# Sht1-Schem.net
KiCad netlist of a schematic drawn in Altium Designer
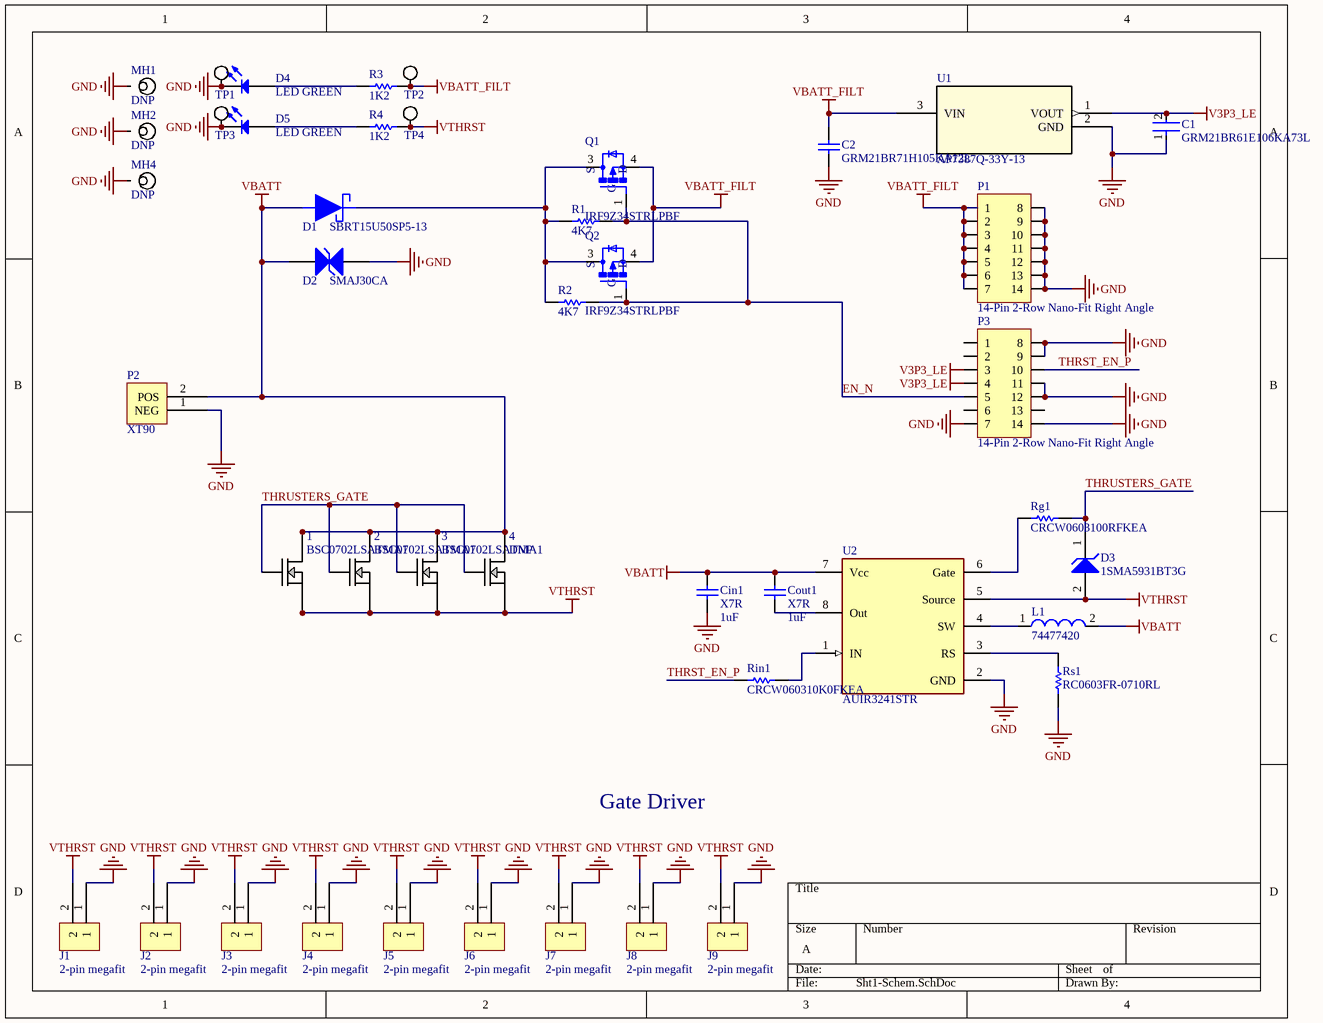
[diagram p0: Sht1-Schem.SchDoc]

(export (version "E")
  (design (tool "Eeschema 10.0.6"))
  (components
    (comp (ref "1")
      (value "BSC0702LSATMA1")
      (footprint "TRANS_NexFET_Q5A")
      (description "No Description Available")
      (fields
        (field (name "MANUFACTURER_PART_NUMBER") "CSD18537NQ5A")
        (field (name "COPYRIGHT") "Copyright (C) 2018 Accelerated Designs. All rights reserved")
      )
      (libsource (lib "TAUV-Lib") (part "BSC0702LSATMA1"))
    )
    (comp (ref "2")
      (value "BSC0702LSATMA1")
      (footprint "TRANS_NexFET_Q5A")
      (description "No Description Available")
      (fields
        (field (name "MANUFACTURER_PART_NUMBER") "CSD18537NQ5A")
        (field (name "COPYRIGHT") "Copyright (C) 2018 Accelerated Designs. All rights reserved")
      )
      (libsource (lib "TAUV-Lib") (part "BSC0702LSATMA1"))
    )
    (comp (ref "3")
      (value "BSC0702LSATMA1")
      (footprint "TRANS_NexFET_Q5A")
      (description "No Description Available")
      (fields
        (field (name "MANUFACTURER_PART_NUMBER") "CSD18537NQ5A")
        (field (name "COPYRIGHT") "Copyright (C) 2018 Accelerated Designs. All rights reserved")
      )
      (libsource (lib "TAUV-Lib") (part "BSC0702LSATMA1"))
    )
    (comp (ref "4")
      (value "DNP")
      (footprint "TRANS_NexFET_Q5A")
      (description "No Description Available")
      (fields
        (field (name "MANUFACTURER_PART_NUMBER") "CSD18537NQ5A")
        (field (name "COPYRIGHT") "Copyright (C) 2018 Accelerated Designs. All rights reserved")
      )
      (libsource (lib "TAUV-Lib") (part "BSC0702LSATMA1"))
    )
    (comp (ref "C1")
      (value "GRM21BR61E106KA73L")
      (footprint "FP-GRM21B-0_15-IPC_C")
      (description "Chip Multilayer Ceramic Capacitors for General Purpose, 0805, 10uF, X5R, 15%, 10%, 25V")
      (fields (field (name "VOLTAGE") "25V") (field (name "TOLERANCE") "10%"))
      (libsource (lib "Altium Content Vault") (part "b4654b650e69147ec39a6b967a45e02"))
    )
    (comp (ref "C2")
      (value "GRM21BR71H105KA12L")
      (footprint "CAPC2013X135X45LL10T25")
      (description "1uF")
      (fields (field (name "MANUFACTURER") "Murata"))
      (libsource (lib "Altium Content Vault") (part "CAP"))
    )
    (comp (ref "Cin1")
      (value "X7R")
      (footprint "C0805")
      (description "Capacitor")
      (fields (field (name "ALTIUM_VALUE") "1uF") (field (name "PUBLISHER") "Altium Limited"))
      (libsource (lib "Miscellaneous Devices") (part "Cap"))
    )
    (comp (ref "Cout1")
      (value "X7R")
      (footprint "C0805")
      (description "Capacitor")
      (fields (field (name "ALTIUM_VALUE") "1uF") (field (name "PUBLISHER") "Altium Limited"))
      (libsource (lib "Miscellaneous Devices") (part "Cap"))
    )
    (comp (ref "D1")
      (value "SBRT15U50SP5-13")
      (footprint "SBRT15U50SP5-13")
      (fields (field (name "MANUFACTURER") "Diodes Incorporated"))
      (libsource (lib "CMR_Miscellaneous_Devices") (part "SBRT15U50SP5-13"))
    )
    (comp (ref "D2")
      (value "SMAJ30CA")
      (footprint "LFUS-DO-214AC-A-2_V")
      (description "Transient Voltage Suppression Diode, 30 V, -65 to 150 degC, 2-Pin SMD, RoHS, Tape and Reel")
      (fields (field (name "MANUFACTURER") "Littelfuse-Inc."))
      (libsource (lib "Altium Content Vault") (part "DZEN-AA-2"))
    )
    (comp (ref "D3")
      (value "1SMA5931BT3G")
      (footprint "ONSC-SMA-2-403D-02_F_V")
      (description "1.5 W Zener Voltage Regulator, 2-Pin SMA, Pb-Free, Tape and Reel")
      (fields (field (name "MANUFACTURER") "On Semiconductor"))
      (libsource (lib "Altium Content Vault") (part "ONSC-K1A2-2"))
    )
    (comp (ref "D4")
      (value "LED GREEN")
      (footprint "LED_0805")
      (description "led")
      (fields
        (field (name "MANUFACTURER") "Lite-On Inc.")
        (field (name "MANUFACTURER PART NUMBER") "LTST-C171KGKT")
      )
      (libsource (lib "CMR_Miscellaneous_Devices") (part "LED0"))
    )
    (comp (ref "D5")
      (value "LED GREEN")
      (footprint "LED_0805")
      (description "led")
      (fields
        (field (name "MANUFACTURER") "Lite-On Inc.")
        (field (name "MANUFACTURER PART NUMBER") "LTST-C171KGKT")
      )
      (libsource (lib "CMR_Miscellaneous_Devices") (part "LED0"))
    )
    (comp (ref "J1")
      (value "2-pin megafit")
      (footprint "2-pin Megafit RA")
      (libsource (lib "TAUV-Lib") (part "2-pin megafit"))
    )
    (comp (ref "J2")
      (value "2-pin megafit")
      (footprint "2-pin Megafit RA")
      (libsource (lib "TAUV-Lib") (part "2-pin megafit"))
    )
    (comp (ref "J3")
      (value "2-pin megafit")
      (footprint "2-pin Megafit RA")
      (libsource (lib "TAUV-Lib") (part "2-pin megafit"))
    )
    (comp (ref "J4")
      (value "2-pin megafit")
      (footprint "2-pin Megafit RA")
      (libsource (lib "TAUV-Lib") (part "2-pin megafit"))
    )
    (comp (ref "J5")
      (value "2-pin megafit")
      (footprint "2-pin Megafit RA")
      (libsource (lib "TAUV-Lib") (part "2-pin megafit"))
    )
    (comp (ref "J6")
      (value "2-pin megafit")
      (footprint "2-pin Megafit RA")
      (libsource (lib "TAUV-Lib") (part "2-pin megafit"))
    )
    (comp (ref "J7")
      (value "2-pin megafit")
      (footprint "2-pin Megafit RA")
      (libsource (lib "TAUV-Lib") (part "2-pin megafit"))
    )
    (comp (ref "J8")
      (value "2-pin megafit")
      (footprint "2-pin Megafit RA")
      (libsource (lib "TAUV-Lib") (part "2-pin megafit"))
    )
    (comp (ref "J9")
      (value "2-pin megafit")
      (footprint "2-pin Megafit RA")
      (libsource (lib "TAUV-Lib") (part "2-pin megafit"))
    )
    (comp (ref "L1")
      (value "74477420")
      (footprint "WE-PD2-M")
      (description "SMD Power Inductor WE-PD2, L = 100 µH")
      (libsource (lib "Altium Content Vault") (part "PAS-IND-INDUCTOR-2"))
    )
    (comp (ref "MH1")
      (value "DNP")
      (footprint "Mounting Hole #4-40")
      (description "Mounting Hole for ANSI #4-40 w/ Flat Washer, Loose Fit")
      (libsource (lib "TAUV-Lib") (part "Mounting Hole #4-40, Loose Fit"))
    )
    (comp (ref "MH2")
      (value "DNP")
      (footprint "Mounting Hole #4-40")
      (description "Mounting Hole for ANSI #4-40 w/ Flat Washer, Loose Fit")
      (libsource (lib "TAUV-Lib") (part "Mounting Hole #4-40, Loose Fit"))
    )
    (comp (ref "MH4")
      (value "DNP")
      (footprint "Mounting Hole #4-40")
      (description "Mounting Hole for ANSI #4-40 w/ Flat Washer, Loose Fit")
      (libsource (lib "TAUV-Lib") (part "Mounting Hole #4-40, Loose Fit"))
    )
    (comp (ref "P1")
      (value "14-Pin 2-Row Nano-Fit Right Angle")
      (footprint "MOLEX NANO-FIT 2X7 - Right Angle")
      (description "NanoFit Right Hdr TH DR 14Ckt")
      (fields (field (name "PART NUMBER") "105314-1214") (field (name "MANUFACTURER") "Molex"))
      (libsource (lib "CMR_Connectors") (part "14-Pin 2-Row Nano-Fit Right Angle"))
    )
    (comp (ref "P2") (value "XT90") (footprint "XT90") (libsource (lib "TAUV-Lib") (part "XT90")))
    (comp (ref "P3")
      (value "14-Pin 2-Row Nano-Fit Right Angle")
      (footprint "MOLEX NANO-FIT 2X7 - Right Angle")
      (description "NanoFit Right Hdr TH DR 14Ckt")
      (fields (field (name "PART NUMBER") "105314-1214") (field (name "MANUFACTURER") "Molex"))
      (libsource (lib "CMR_Connectors") (part "14-Pin 2-Row Nano-Fit Right Angle"))
    )
    (comp (ref "Q1")
      (value "IRF9Z34STRLPBF")
      (footprint "TO254P1521X483-4N")
      (description "P-Channel 60V 18A _Tc_ 3.7W _Ta_, 88W _Tc_ Surface Mount D2PAK")
      (fields (field (name "MF") "Vishay"))
      (libsource (lib "TAUV-Lib") (part "IRF9Z34STRLPBF"))
    )
    (comp (ref "Q2")
      (value "IRF9Z34STRLPBF")
      (footprint "TO254P1521X483-4N")
      (description "P-Channel 60V 18A _Tc_ 3.7W _Ta_, 88W _Tc_ Surface Mount D2PAK")
      (fields (field (name "MF") "Vishay"))
      (libsource (lib "TAUV-Lib") (part "IRF9Z34STRLPBF"))
    )
    (comp (ref "R1")
      (value "4K7")
      (footprint "RESC0603(1608)_L")
      (description "4K7 0.1W 1% 0603 (1608 Metric)  SMD")
      (fields (field (name "POWER") "0.1 W") (field (name "TOLERANCE") "1 %"))
      (libsource (lib "Altium Content Vault") (part "RES"))
    )
    (comp (ref "R2")
      (value "4K7")
      (footprint "RESC0603(1608)_L")
      (description "4K7 0.1W 1% 0603 (1608 Metric)  SMD")
      (fields (field (name "POWER") "0.1 W") (field (name "TOLERANCE") "1 %"))
      (libsource (lib "Altium Content Vault") (part "RES"))
    )
    (comp (ref "R3")
      (value "1K2")
      (footprint "RESC0603(1608)_L")
      (description "1K2 0.1W 1% 0603 (1608 Metric)  SMD")
      (fields (field (name "POWER") "0.1 W") (field (name "TOLERANCE") "1 %"))
      (libsource (lib "Altium Content Vault") (part "RES"))
    )
    (comp (ref "R4")
      (value "1K2")
      (footprint "RESC0603(1608)_L")
      (description "1K2 0.1W 1% 0603 (1608 Metric)  SMD")
      (fields (field (name "POWER") "0.1 W") (field (name "TOLERANCE") "1 %"))
      (libsource (lib "Altium Content Vault") (part "RES"))
    )
    (comp (ref "Rg1")
      (value "CRCW0603100RFKEA")
      (footprint "RESC1609X50X30ML8T20")
      (description "Chip Resistor, 100 Ohm, +/- 1%, 100 mW,-55 to 155 degC, 0603 (1608 Metric), RoHS, Tape and Ree")
      (fields (field (name "MANUFACTURER") "Vishay Semiconductor"))
      (libsource (lib "Altium Content Vault") (part "RES-2"))
    )
    (comp (ref "Rin1")
      (value "CRCW060310K0FKEA")
      (footprint "RESC1609X50X30NL8T20")
      (description "Chip Resistor, 10 KOhm, +/- 1%, 100 mW, -55 to 155 degC, 0603 (1608 Metric), RoHS, Tape and Reel")
      (fields (field (name "MANUFACTURER") "Vishay Semiconductor"))
      (libsource (lib "Altium Content Vault") (part "RES-2"))
    )
    (comp (ref "Rs1")
      (value "RC0603FR-0710RL")
      (footprint "RESC1608X55X25NL10T15")
      (description "Chip Resistor, 10 Ohm, +/- 1%, 0.1 W, -55 to 155 degC, 0603 (1608 Metric), RoHS, Tape and Reel")
      (fields (field (name "MANUFACTURER") "Yageo"))
      (libsource (lib "Altium Content Vault") (part "RES-2"))
    )
    (comp (ref "TP1")
      (value "Test Point Loop")
      (footprint "Test Point Loop - Black")
      (description "Keyston Electronics 5001 Test Point Loop")
      (fields (field (name "MANUFACTURER") "Keystone Electronics"))
      (libsource (lib "CMR_PCB_Components") (part "Test Point Loop"))
    )
    (comp (ref "TP2")
      (value "Test Point Loop")
      (footprint "Test Point Loop - Black")
      (description "Keyston Electronics 5001 Test Point Loop")
      (fields (field (name "MANUFACTURER") "Keystone Electronics"))
      (libsource (lib "CMR_PCB_Components") (part "Test Point Loop"))
    )
    (comp (ref "TP3")
      (value "Test Point Loop")
      (footprint "Test Point Loop - Black")
      (description "Keyston Electronics 5001 Test Point Loop")
      (fields (field (name "MANUFACTURER") "Keystone Electronics"))
      (libsource (lib "CMR_PCB_Components") (part "Test Point Loop"))
    )
    (comp (ref "TP4")
      (value "Test Point Loop")
      (footprint "Test Point Loop - Black")
      (description "Keyston Electronics 5001 Test Point Loop")
      (fields (field (name "MANUFACTURER") "Keystone Electronics"))
      (libsource (lib "CMR_PCB_Components") (part "Test Point Loop"))
    )
    (comp (ref "U1")
      (value "AP7387Q-33Y-13")
      (footprint "SOT-89-3_2P7X4P7_ONS")
      (description "No Description Available")
      (libsource (lib "TAUV-Lib") (part "AP7387Q-33Y-13"))
    )
    (comp (ref "U2")
      (value "AUIR3241STR")
      (footprint "FP-PG-DSO-8-MFG")
      (description "IC GATE DRVR HIGH-SIDE 8SO")
      (libsource (lib "Altium Content Vault") (part "34ae5cb6024c322bdcbf0313f74d293"))
    )
  )
  (nets
    (net (code "1") (name "/EN_N") (class "Default")
      (node (ref "P3") (pin "5") (pinfunction "5_5") (pintype "passive"))
      (node (ref "Q1") (pin "1") (pinfunction "G_1") (pintype "passive"))
      (node (ref "Q2") (pin "1") (pinfunction "G_1") (pintype "passive"))
      (node (ref "R1") (pin "1") (pinfunction "1_1") (pintype "passive"))
      (node (ref "R2") (pin "1") (pinfunction "1_1") (pintype "passive"))
    )
    (net (code "2") (name "/THRST_EN_P") (class "Default")
      (node (ref "P3") (pin "10") (pinfunction "10_10") (pintype "passive"))
      (node (ref "Rin1") (pin "1") (pinfunction "1_1") (pintype "passive"))
    )
    (net (code "3") (name "/THRUSTERS_GATE") (class "Default")
      (node (ref "1") (pin "4") (pinfunction "Gate_4") (pintype "passive"))
      (node (ref "2") (pin "4") (pinfunction "Gate_4") (pintype "passive"))
      (node (ref "3") (pin "4") (pinfunction "Gate_4") (pintype "passive"))
      (node (ref "4") (pin "4") (pinfunction "Gate_4") (pintype "passive"))
      (node (ref "D3") (pin "1") (pinfunction "K_1") (pintype "passive"))
      (node (ref "Rg1") (pin "2") (pinfunction "2_2") (pintype "passive"))
    )
    (net (code "4") (name "GND") (class "Default")
      (node (ref "C1") (pin "1") (pinfunction "1_1") (pintype "passive"))
      (node (ref "C2") (pin "1") (pinfunction "1_1") (pintype "passive"))
      (node (ref "Cin1") (pin "1") (pinfunction "1_1") (pintype "passive"))
      (node (ref "D2") (pin "2") (pinfunction "A_2") (pintype "passive"))
      (node (ref "D4") (pin "1") (pinfunction "K_1") (pintype "passive"))
      (node (ref "D5") (pin "1") (pinfunction "K_1") (pintype "passive"))
      (node (ref "J1") (pin "1") (pinfunction "1_1") (pintype "passive"))
      (node (ref "J2") (pin "1") (pinfunction "1_1") (pintype "passive"))
      (node (ref "J3") (pin "1") (pinfunction "1_1") (pintype "passive"))
      (node (ref "J4") (pin "1") (pinfunction "1_1") (pintype "passive"))
      (node (ref "J5") (pin "1") (pinfunction "1_1") (pintype "passive"))
      (node (ref "J6") (pin "1") (pinfunction "1_1") (pintype "passive"))
      (node (ref "J7") (pin "1") (pinfunction "1_1") (pintype "passive"))
      (node (ref "J8") (pin "1") (pinfunction "1_1") (pintype "passive"))
      (node (ref "J9") (pin "1") (pinfunction "1_1") (pintype "passive"))
      (node (ref "MH1") (pin "0") (pinfunction "0_0") (pintype "passive"))
      (node (ref "MH2") (pin "0") (pinfunction "0_0") (pintype "passive"))
      (node (ref "MH4") (pin "0") (pinfunction "0_0") (pintype "passive"))
      (node (ref "P1") (pin "10") (pinfunction "10_10") (pintype "passive"))
      (node (ref "P1") (pin "11") (pinfunction "11_11") (pintype "passive"))
      (node (ref "P1") (pin "12") (pinfunction "12_12") (pintype "passive"))
      (node (ref "P1") (pin "13") (pinfunction "13_13") (pintype "passive"))
      (node (ref "P1") (pin "14") (pinfunction "14_14") (pintype "passive"))
      (node (ref "P1") (pin "8") (pinfunction "8_8") (pintype "passive"))
      (node (ref "P1") (pin "9") (pinfunction "9_9") (pintype "passive"))
      (node (ref "P2") (pin "1") (pinfunction "NEG_1") (pintype "passive"))
      (node (ref "P3") (pin "11") (pinfunction "11_11") (pintype "passive"))
      (node (ref "P3") (pin "12") (pinfunction "12_12") (pintype "passive"))
      (node (ref "P3") (pin "14") (pinfunction "14_14") (pintype "passive"))
      (node (ref "P3") (pin "7") (pinfunction "7_7") (pintype "passive"))
      (node (ref "P3") (pin "8") (pinfunction "8_8") (pintype "passive"))
      (node (ref "P3") (pin "9") (pinfunction "9_9") (pintype "passive"))
      (node (ref "Rs1") (pin "1") (pinfunction "1_1") (pintype "passive"))
      (node (ref "TP1") (pin "1") (pinfunction "1_1") (pintype "passive"))
      (node (ref "TP3") (pin "1") (pinfunction "1_1") (pintype "passive"))
      (node (ref "U1") (pin "2") (pinfunction "GND_2") (pintype "power_in"))
      (node (ref "U2") (pin "2") (pinfunction "GND_2") (pintype "power_in"))
    )
    (net (code "5") (name "Net-(D4-A)") (class "Default")
      (node (ref "D4") (pin "2") (pinfunction "A_2") (pintype "passive"))
      (node (ref "R3") (pin "1") (pinfunction "1_1") (pintype "passive"))
    )
    (net (code "6") (name "Net-(D5-A)") (class "Default")
      (node (ref "D5") (pin "2") (pinfunction "A_2") (pintype "passive"))
      (node (ref "R4") (pin "1") (pinfunction "1_1") (pintype "passive"))
    )
    (net (code "7") (name "Net-(Q1-S)") (class "Default")
      (node (ref "D1") (pin "2") (pinfunction "2_2") (pintype "passive"))
      (node (ref "Q1") (pin "3") (pinfunction "S_3") (pintype "passive"))
      (node (ref "Q2") (pin "3") (pinfunction "S_3") (pintype "passive"))
      (node (ref "R1") (pin "2") (pinfunction "2_2") (pintype "passive"))
      (node (ref "R2") (pin "2") (pinfunction "2_2") (pintype "passive"))
    )
    (net (code "8") (name "Net-(U2-Gate)") (class "Default")
      (node (ref "Rg1") (pin "1") (pinfunction "1_1") (pintype "passive"))
      (node (ref "U2") (pin "6") (pinfunction "Gate_6") (pintype "passive"))
    )
    (net (code "9") (name "Net-(U2-IN)") (class "Default")
      (node (ref "Rin1") (pin "2") (pinfunction "2_2") (pintype "passive"))
      (node (ref "U2") (pin "1") (pinfunction "IN_1") (pintype "input"))
    )
    (net (code "10") (name "Net-(U2-Out)") (class "Default")
      (node (ref "Cout1") (pin "1") (pinfunction "1_1") (pintype "passive"))
      (node (ref "U2") (pin "8") (pinfunction "Out_8") (pintype "passive"))
    )
    (net (code "11") (name "Net-(U2-RS)") (class "Default")
      (node (ref "Rs1") (pin "2") (pinfunction "2_2") (pintype "passive"))
      (node (ref "U2") (pin "3") (pinfunction "RS_3") (pintype "passive"))
    )
    (net (code "12") (name "Net-(U2-SW)") (class "Default")
      (node (ref "L1") (pin "1") (pinfunction "1_1") (pintype "passive"))
      (node (ref "U2") (pin "4") (pinfunction "SW_4") (pintype "passive"))
    )
    (net (code "13") (name "V3P3_LE") (class "Default")
      (node (ref "C1") (pin "2") (pinfunction "2_2") (pintype "passive"))
      (node (ref "P3") (pin "3") (pinfunction "3_3") (pintype "passive"))
      (node (ref "P3") (pin "4") (pinfunction "4_4") (pintype "passive"))
      (node (ref "U1") (pin "1") (pinfunction "VOUT_1") (pintype "output"))
    )
    (net (code "14") (name "VBATT") (class "Default")
      (node (ref "1") (pin "5") (pinfunction "Drain_5") (pintype "passive"))
      (node (ref "1") (pin "6") (pinfunction "Drain_6") (pintype "passive"))
      (node (ref "1") (pin "7") (pinfunction "Drain_7") (pintype "passive"))
      (node (ref "1") (pin "8") (pinfunction "Drain_8") (pintype "passive"))
      (node (ref "1") (pin "9") (pinfunction "Drain_9") (pintype "passive"))
      (node (ref "2") (pin "5") (pinfunction "Drain_5") (pintype "passive"))
      (node (ref "2") (pin "6") (pinfunction "Drain_6") (pintype "passive"))
      (node (ref "2") (pin "7") (pinfunction "Drain_7") (pintype "passive"))
      (node (ref "2") (pin "8") (pinfunction "Drain_8") (pintype "passive"))
      (node (ref "2") (pin "9") (pinfunction "Drain_9") (pintype "passive"))
      (node (ref "3") (pin "5") (pinfunction "Drain_5") (pintype "passive"))
      (node (ref "3") (pin "6") (pinfunction "Drain_6") (pintype "passive"))
      (node (ref "3") (pin "7") (pinfunction "Drain_7") (pintype "passive"))
      (node (ref "3") (pin "8") (pinfunction "Drain_8") (pintype "passive"))
      (node (ref "3") (pin "9") (pinfunction "Drain_9") (pintype "passive"))
      (node (ref "4") (pin "5") (pinfunction "Drain_5") (pintype "passive"))
      (node (ref "4") (pin "6") (pinfunction "Drain_6") (pintype "passive"))
      (node (ref "4") (pin "7") (pinfunction "Drain_7") (pintype "passive"))
      (node (ref "4") (pin "8") (pinfunction "Drain_8") (pintype "passive"))
      (node (ref "4") (pin "9") (pinfunction "Drain_9") (pintype "passive"))
      (node (ref "Cin1") (pin "2") (pinfunction "2_2") (pintype "passive"))
      (node (ref "Cout1") (pin "2") (pinfunction "2_2") (pintype "passive"))
      (node (ref "D1") (pin "1") (pinfunction "1_1") (pintype "passive"))
      (node (ref "D2") (pin "1") (pinfunction "A_1") (pintype "passive"))
      (node (ref "L1") (pin "2") (pinfunction "2_2") (pintype "passive"))
      (node (ref "P2") (pin "2") (pinfunction "POS_2") (pintype "passive"))
      (node (ref "U2") (pin "7") (pinfunction "Vcc_7") (pintype "power_in"))
    )
    (net (code "15") (name "VBATT_FILT") (class "Default")
      (node (ref "C2") (pin "2") (pinfunction "2_2") (pintype "passive"))
      (node (ref "P1") (pin "1") (pinfunction "1_1") (pintype "passive"))
      (node (ref "P1") (pin "2") (pinfunction "2_2") (pintype "passive"))
      (node (ref "P1") (pin "3") (pinfunction "3_3") (pintype "passive"))
      (node (ref "P1") (pin "4") (pinfunction "4_4") (pintype "passive"))
      (node (ref "P1") (pin "5") (pinfunction "5_5") (pintype "passive"))
      (node (ref "P1") (pin "6") (pinfunction "6_6") (pintype "passive"))
      (node (ref "P1") (pin "7") (pinfunction "7_7") (pintype "passive"))
      (node (ref "Q1") (pin "4") (pinfunction "D_4") (pintype "passive"))
      (node (ref "Q2") (pin "4") (pinfunction "D_4") (pintype "passive"))
      (node (ref "R3") (pin "2") (pinfunction "2_2") (pintype "passive"))
      (node (ref "TP2") (pin "1") (pinfunction "1_1") (pintype "passive"))
      (node (ref "U1") (pin "3") (pinfunction "VIN_3") (pintype "passive"))
    )
    (net (code "16") (name "VTHRST") (class "Default")
      (node (ref "1") (pin "1") (pinfunction "Source_1") (pintype "passive"))
      (node (ref "1") (pin "2") (pinfunction "Source_2") (pintype "passive"))
      (node (ref "1") (pin "3") (pinfunction "Source_3") (pintype "passive"))
      (node (ref "2") (pin "1") (pinfunction "Source_1") (pintype "passive"))
      (node (ref "2") (pin "2") (pinfunction "Source_2") (pintype "passive"))
      (node (ref "2") (pin "3") (pinfunction "Source_3") (pintype "passive"))
      (node (ref "3") (pin "1") (pinfunction "Source_1") (pintype "passive"))
      (node (ref "3") (pin "2") (pinfunction "Source_2") (pintype "passive"))
      (node (ref "3") (pin "3") (pinfunction "Source_3") (pintype "passive"))
      (node (ref "4") (pin "1") (pinfunction "Source_1") (pintype "passive"))
      (node (ref "4") (pin "2") (pinfunction "Source_2") (pintype "passive"))
      (node (ref "4") (pin "3") (pinfunction "Source_3") (pintype "passive"))
      (node (ref "D3") (pin "2") (pinfunction "A_2") (pintype "passive"))
      (node (ref "J1") (pin "2") (pinfunction "2_2") (pintype "passive"))
      (node (ref "J2") (pin "2") (pinfunction "2_2") (pintype "passive"))
      (node (ref "J3") (pin "2") (pinfunction "2_2") (pintype "passive"))
      (node (ref "J4") (pin "2") (pinfunction "2_2") (pintype "passive"))
      (node (ref "J5") (pin "2") (pinfunction "2_2") (pintype "passive"))
      (node (ref "J6") (pin "2") (pinfunction "2_2") (pintype "passive"))
      (node (ref "J7") (pin "2") (pinfunction "2_2") (pintype "passive"))
      (node (ref "J8") (pin "2") (pinfunction "2_2") (pintype "passive"))
      (node (ref "J9") (pin "2") (pinfunction "2_2") (pintype "passive"))
      (node (ref "R4") (pin "2") (pinfunction "2_2") (pintype "passive"))
      (node (ref "TP4") (pin "1") (pinfunction "1_1") (pintype "passive"))
      (node (ref "U2") (pin "5") (pinfunction "Source_5") (pintype "passive"))
    )
    (net (code "17") (name "unconnected-(P3-Pad1)") (class "Default")
      (node (ref "P3") (pin "1") (pinfunction "1_1") (pintype "passive"))
    )
    (net (code "18") (name "unconnected-(P3-Pad2)") (class "Default")
      (node (ref "P3") (pin "2") (pinfunction "2_2") (pintype "passive"))
    )
    (net (code "19") (name "unconnected-(P3-Pad6)") (class "Default")
      (node (ref "P3") (pin "6") (pinfunction "6_6") (pintype "passive"))
    )
    (net (code "20") (name "unconnected-(P3-Pad13)") (class "Default")
      (node (ref "P3") (pin "13") (pinfunction "13_13") (pintype "passive"))
    )
  )
)
